# Sheet1.net
KiCad netlist of a schematic drawn in Altium Designer
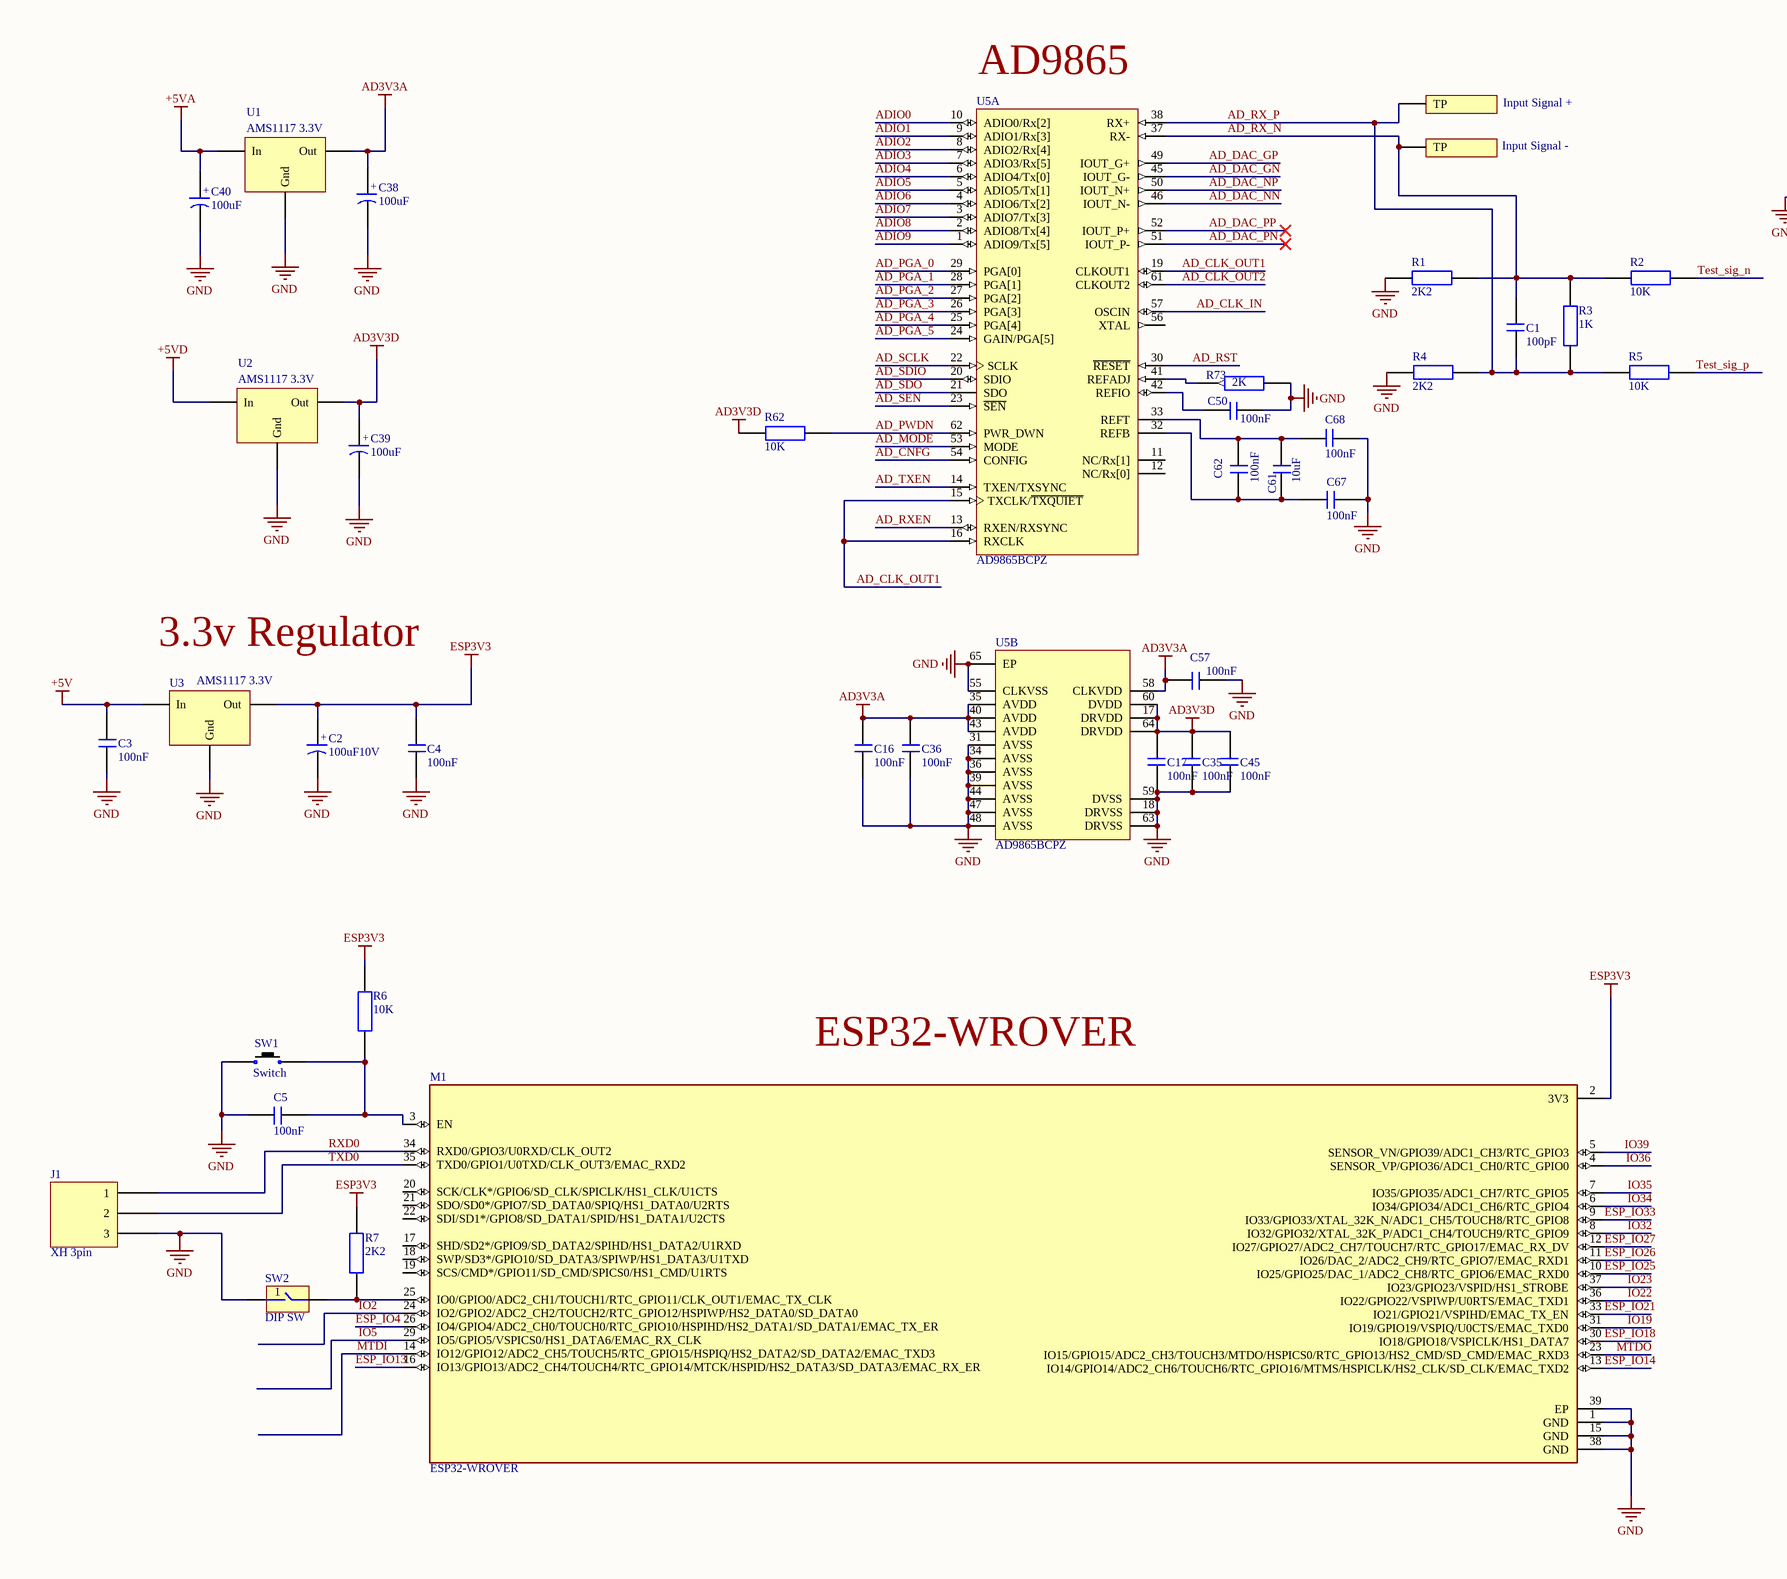
[diagram p0: Sheet1.SchDoc, left]
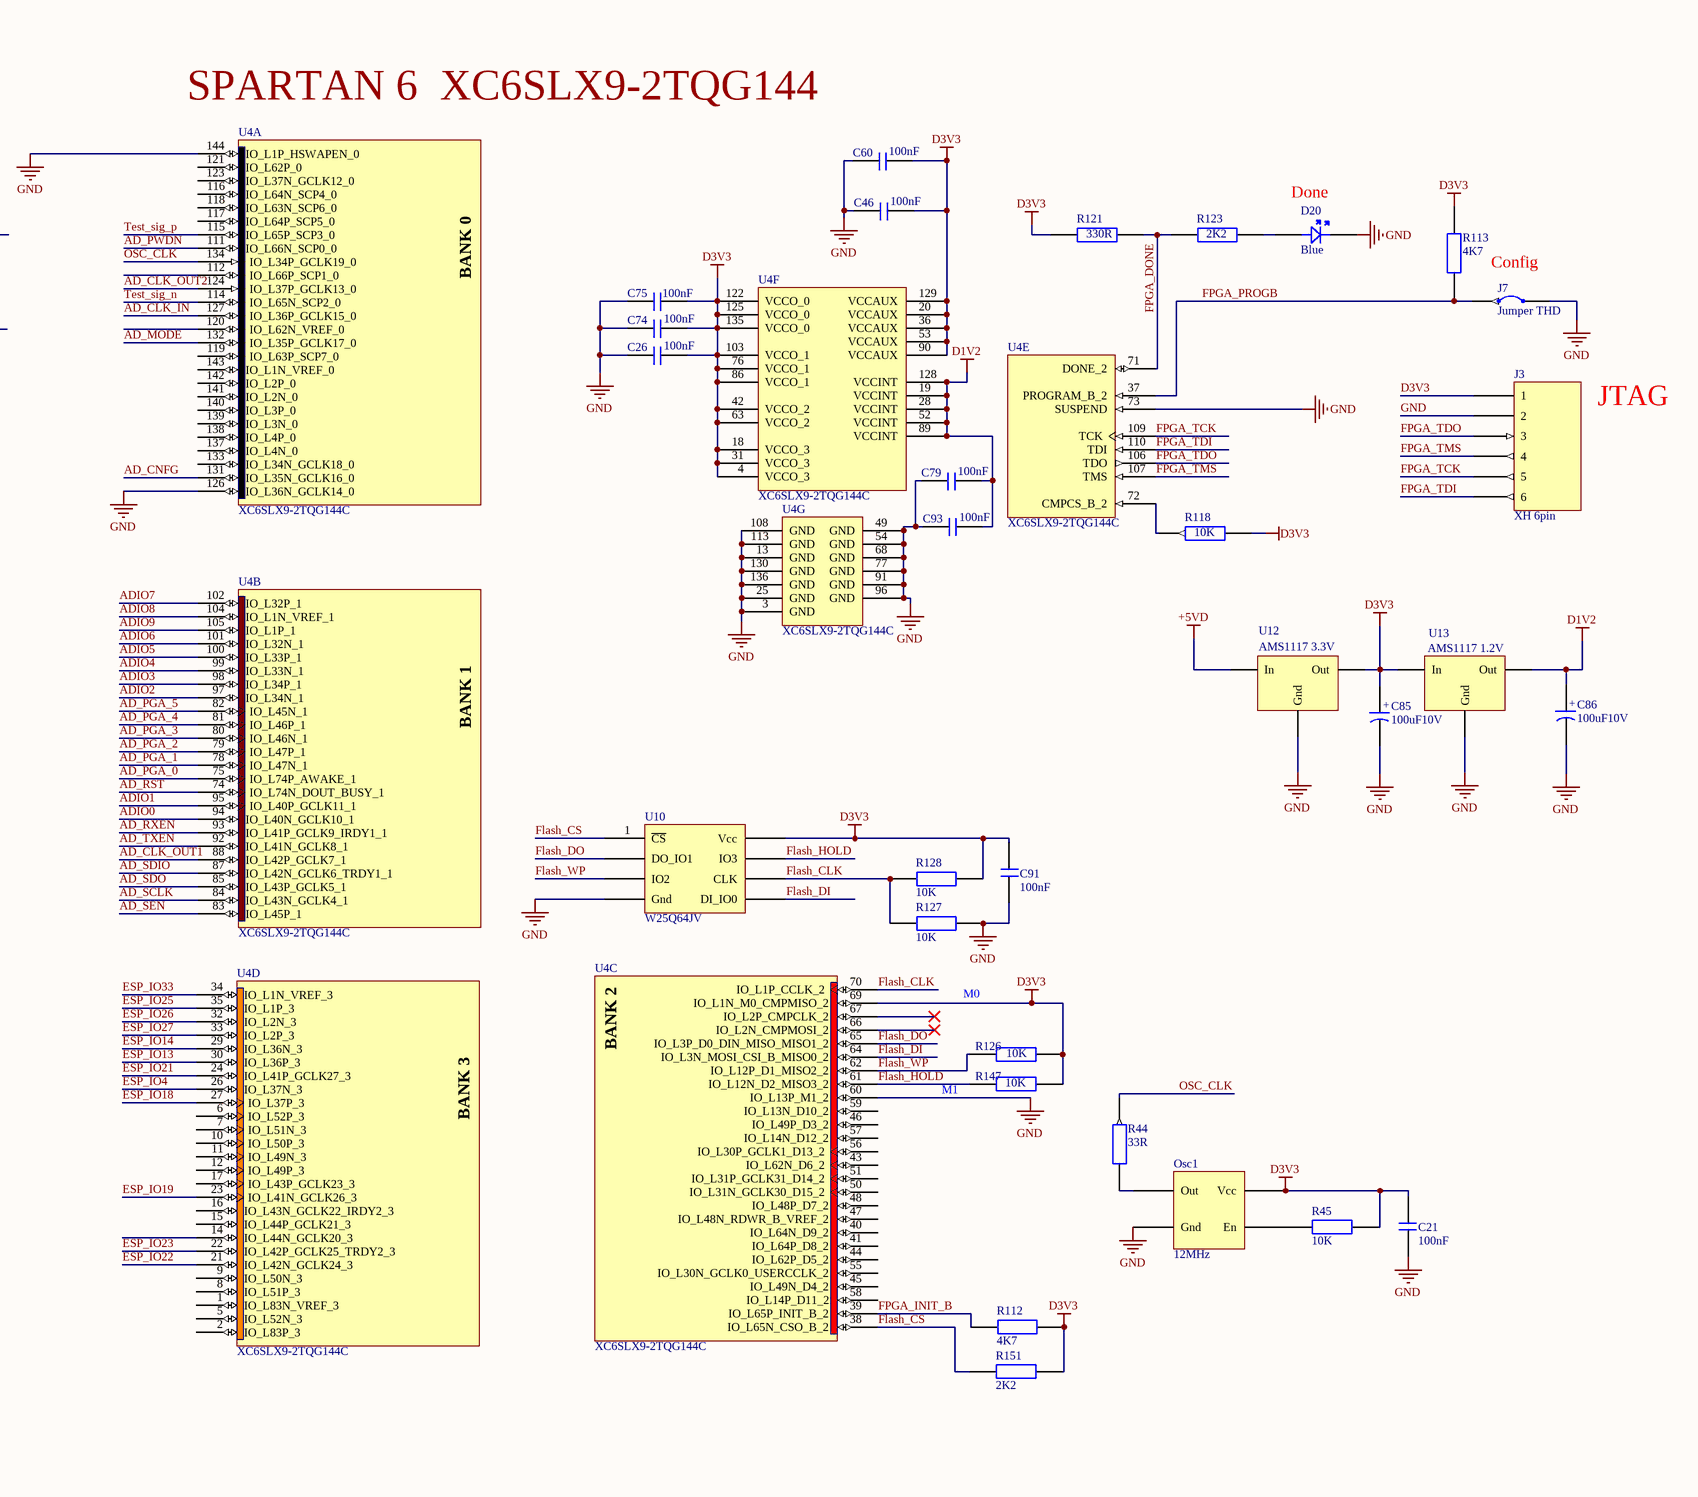
[diagram p1: Sheet1.SchDoc, right]

(export (version "E")
  (design (tool "Eeschema 10.0.6"))
  (components
    (comp (ref "C1")
      (value "100pF")
      (footprint "CAP_0805")
      (description "Capacitor SMD 0805")
      (libsource (lib "My_Integrated_Library") (part "Cap0805"))
    )
    (comp (ref "C2")
      (value "100uF10V")
      (footprint "Cap_Tan_Size_B")
      (description "Capacitor SMD Tantalium Size B")
      (libsource (lib "My_Integrated_Library") (part "Cap_Tant_B"))
    )
    (comp (ref "C3")
      (value "100nF")
      (footprint "CAP_0805")
      (description "Capacitor SMD 0805")
      (libsource (lib "My_Integrated_Library") (part "Cap0805"))
    )
    (comp (ref "C4")
      (value "100nF")
      (footprint "CAP_0805")
      (description "Capacitor SMD 0805")
      (libsource (lib "My_Integrated_Library") (part "Cap0805"))
    )
    (comp (ref "C5")
      (value "100nF")
      (footprint "CAP_0805")
      (description "Capacitor SMD 0805")
      (libsource (lib "My_Integrated_Library") (part "Cap0805"))
    )
    (comp (ref "C16")
      (value "100nF")
      (footprint "CAP_0805")
      (description "Capacitor SMD 0805")
      (libsource (lib "My_Integrated_Library") (part "Cap0805"))
    )
    (comp (ref "C17")
      (value "100nF")
      (footprint "CAP_0805")
      (description "Capacitor SMD 0805")
      (libsource (lib "My_Integrated_Library") (part "Cap0805"))
    )
    (comp (ref "C21")
      (value "100nF")
      (footprint "CAP_0805")
      (description "Capacitor SMD 0805")
      (libsource (lib "My_Integrated_Library") (part "Cap0805"))
    )
    (comp (ref "C26")
      (value "100nF")
      (footprint "CAP_0805")
      (description "Capacitor SMD 0805")
      (libsource (lib "My_Integrated_Library") (part "Cap0805"))
    )
    (comp (ref "C35")
      (value "100nF")
      (footprint "CAP_0805")
      (description "Capacitor SMD 0805")
      (libsource (lib "My_Integrated_Library") (part "Cap0805"))
    )
    (comp (ref "C36")
      (value "100nF")
      (footprint "CAP_0805")
      (description "Capacitor SMD 0805")
      (libsource (lib "My_Integrated_Library") (part "Cap0805"))
    )
    (comp (ref "C38")
      (value "100uF")
      (footprint "Cap_Tan_Size_B")
      (description "Capacitor SMD Tantalium Size B")
      (libsource (lib "My_Integrated_Library") (part "Cap_Tant_B"))
    )
    (comp (ref "C39")
      (value "100uF")
      (footprint "Cap_Tan_Size_B")
      (description "Capacitor SMD Tantalium Size B")
      (libsource (lib "My_Integrated_Library") (part "Cap_Tant_B"))
    )
    (comp (ref "C40")
      (value "100uF")
      (footprint "Cap_Tan_Size_B")
      (description "Capacitor SMD Tantalium Size B")
      (libsource (lib "My_Integrated_Library") (part "Cap_Tant_B"))
    )
    (comp (ref "C45")
      (value "100nF")
      (footprint "CAP_0805")
      (description "Capacitor SMD 0805")
      (libsource (lib "My_Integrated_Library") (part "Cap0805"))
    )
    (comp (ref "C46")
      (value "100nF")
      (footprint "CAP_0805")
      (description "Capacitor SMD 0805")
      (libsource (lib "My_Integrated_Library") (part "Cap0805"))
    )
    (comp (ref "C50")
      (value "100nF")
      (footprint "CAP_0805")
      (description "Capacitor SMD 0805")
      (libsource (lib "My_Integrated_Library") (part "Cap0805"))
    )
    (comp (ref "C57")
      (value "100nF")
      (footprint "CAP_0805")
      (description "Capacitor SMD 0805")
      (libsource (lib "My_Integrated_Library") (part "Cap0805"))
    )
    (comp (ref "C60")
      (value "100nF")
      (footprint "CAP_0805")
      (description "Capacitor SMD 0805")
      (libsource (lib "My_Integrated_Library") (part "Cap0805"))
    )
    (comp (ref "C61")
      (value "10uF")
      (footprint "CAP_0805")
      (description "Capacitor SMD 0805")
      (libsource (lib "My_Integrated_Library") (part "Cap0805"))
    )
    (comp (ref "C62")
      (value "100nF")
      (footprint "CAP_0805")
      (description "Capacitor SMD 0805")
      (libsource (lib "My_Integrated_Library") (part "Cap0805"))
    )
    (comp (ref "C67")
      (value "100nF")
      (footprint "CAP_0805")
      (description "Capacitor SMD 0805")
      (libsource (lib "My_Integrated_Library") (part "Cap0805"))
    )
    (comp (ref "C68")
      (value "100nF")
      (footprint "CAP_0805")
      (description "Capacitor SMD 0805")
      (libsource (lib "My_Integrated_Library") (part "Cap0805"))
    )
    (comp (ref "C74")
      (value "100nF")
      (footprint "CAP_0805")
      (description "Capacitor SMD 0805")
      (libsource (lib "My_Integrated_Library") (part "Cap0805"))
    )
    (comp (ref "C75")
      (value "100nF")
      (footprint "CAP_0805")
      (description "Capacitor SMD 0805")
      (libsource (lib "My_Integrated_Library") (part "Cap0805"))
    )
    (comp (ref "C79")
      (value "100nF")
      (footprint "CAP_0805")
      (description "Capacitor SMD 0805")
      (libsource (lib "My_Integrated_Library") (part "Cap0805"))
    )
    (comp (ref "C85")
      (value "100uF10V")
      (footprint "Cap_Tan_Size_B")
      (description "Capacitor SMD Tantalium Size B")
      (libsource (lib "My_Integrated_Library") (part "Cap_Tant_B"))
    )
    (comp (ref "C86")
      (value "100uF10V")
      (footprint "Cap_Tan_Size_B")
      (description "Capacitor SMD Tantalium Size B")
      (libsource (lib "My_Integrated_Library") (part "Cap_Tant_B"))
    )
    (comp (ref "C91")
      (value "100nF")
      (footprint "CAP_0805")
      (description "Capacitor SMD 0805")
      (libsource (lib "My_Integrated_Library") (part "Cap0805"))
    )
    (comp (ref "C93")
      (value "100nF")
      (footprint "CAP_0805")
      (description "Capacitor SMD 0805")
      (libsource (lib "My_Integrated_Library") (part "Cap0805"))
    )
    (comp (ref "D20")
      (value "Blue")
      (footprint "LED_0805_Blue")
      (description "LED SMD 0805 Blue")
      (libsource (lib "My_Integrated_Library") (part "LED_0805_Blue"))
    )
    (comp (ref "J1")
      (value "XH 3pin")
      (footprint "XH-3pin")
      (description "Connector XH Female 3-pin")
      (libsource (lib "My_Integrated_Library") (part "Con_XH_3pin"))
    )
    (comp (ref "J3")
      (value "XH 6pin")
      (footprint "XH-6pin")
      (description "Connector XH Female 6-pin")
      (libsource (lib "My_Integrated_Library") (part "Con_XH_6pin"))
    )
    (comp (ref "J7")
      (value "Jumper THD")
      (footprint "Jumper_2pin")
      (description "Jumper pin header + jumper 2pin pirch=2.54mm")
      (libsource (lib "My_Integrated_Library") (part "Jumper DIP"))
    )
    (comp (ref "M1")
      (value "ESP32-WROVER")
      (footprint "ESP32-WROVER")
      (fields (field (name "MF") "Espressif Systems"))
      (libsource (lib "My_Integrated_Library") (part "ESP32-WROVER"))
    )
    (comp (ref "Osc1")
      (value "12MHz")
      (footprint "Osc_SMD_5x7")
      (description "Oscillator SMD 5x7")
      (libsource (lib "My_Integrated_Library") (part "Osc_SMD"))
    )
    (comp (ref "R1")
      (value "2K2")
      (footprint "RES_0805")
      (description "Resistor SMD 0805")
      (libsource (lib "My_Integrated_Library") (part "Res0805"))
    )
    (comp (ref "R2")
      (value "10K")
      (footprint "RES_0805")
      (description "Resistor SMD 0805")
      (libsource (lib "My_Integrated_Library") (part "Res0805"))
    )
    (comp (ref "R3")
      (value "1K")
      (footprint "RES_0805")
      (description "Resistor SMD 0805")
      (libsource (lib "My_Integrated_Library") (part "Res0805"))
    )
    (comp (ref "R4")
      (value "2K2")
      (footprint "RES_0805")
      (description "Resistor SMD 0805")
      (libsource (lib "My_Integrated_Library") (part "Res0805"))
    )
    (comp (ref "R5")
      (value "10K")
      (footprint "RES_0805")
      (description "Resistor SMD 0805")
      (libsource (lib "My_Integrated_Library") (part "Res0805"))
    )
    (comp (ref "R6")
      (value "10K")
      (footprint "RES_0805")
      (description "Resistor SMD 0805")
      (libsource (lib "My_Integrated_Library") (part "Res0805"))
    )
    (comp (ref "R7")
      (value "2K2")
      (footprint "RES_0805")
      (description "Resistor SMD 0805")
      (libsource (lib "My_Integrated_Library") (part "Res0805"))
    )
    (comp (ref "R44")
      (value "33R")
      (footprint "RES_0805")
      (description "Resistor SMD 0805")
      (libsource (lib "My_Integrated_Library") (part "Res0805"))
    )
    (comp (ref "R45")
      (value "10K")
      (footprint "RES_0805")
      (description "Resistor SMD 0805")
      (libsource (lib "My_Integrated_Library") (part "Res0805"))
    )
    (comp (ref "R62")
      (value "10K")
      (footprint "RES_0805")
      (description "Resistor SMD 0805")
      (libsource (lib "My_Integrated_Library") (part "Res0805"))
    )
    (comp (ref "R73")
      (value "2K")
      (footprint "RES_0805")
      (description "Resistor SMD 0805")
      (libsource (lib "My_Integrated_Library") (part "Res0805"))
    )
    (comp (ref "R112")
      (value "4K7")
      (footprint "RES_0805")
      (description "Resistor SMD 0805")
      (libsource (lib "My_Integrated_Library") (part "Res0805"))
    )
    (comp (ref "R113")
      (value "4K7")
      (footprint "RES_0805")
      (description "Resistor SMD 0805")
      (libsource (lib "My_Integrated_Library") (part "Res0805"))
    )
    (comp (ref "R118")
      (value "10K")
      (footprint "RES_0805")
      (description "Resistor SMD 0805")
      (libsource (lib "My_Integrated_Library") (part "Res0805"))
    )
    (comp (ref "R121")
      (value "330R")
      (footprint "RES_0805")
      (description "Resistor SMD 0805")
      (libsource (lib "My_Integrated_Library") (part "Res0805"))
    )
    (comp (ref "R123")
      (value "2K2")
      (footprint "RES_0805")
      (description "Resistor SMD 0805")
      (libsource (lib "My_Integrated_Library") (part "Res0805"))
    )
    (comp (ref "R126")
      (value "10K")
      (footprint "RES_0805")
      (description "Resistor SMD 0805")
      (libsource (lib "My_Integrated_Library") (part "Res0805"))
    )
    (comp (ref "R127")
      (value "10K")
      (footprint "RES_0805")
      (description "Resistor SMD 0805")
      (libsource (lib "My_Integrated_Library") (part "Res0805"))
    )
    (comp (ref "R128")
      (value "10K")
      (footprint "RES_0805")
      (description "Resistor SMD 0805")
      (libsource (lib "My_Integrated_Library") (part "Res0805"))
    )
    (comp (ref "R147")
      (value "10K")
      (footprint "RES_0805")
      (description "Resistor SMD 0805")
      (libsource (lib "My_Integrated_Library") (part "Res0805"))
    )
    (comp (ref "R151")
      (value "2K2")
      (footprint "RES_0805")
      (description "Resistor SMD 0805")
      (libsource (lib "My_Integrated_Library") (part "Res0805"))
    )
    (comp (ref "SW1")
      (value "Switch")
      (footprint "Tact_SW_SMD")
      (description "Tact switch SMD 2pin")
      (libsource (lib "My_Integrated_Library") (part "Tact_sw"))
    )
    (comp (ref "SW2")
      (value "DIP SW")
      (footprint "DIP_SW_1key")
      (description "DIP Swtich 1 key")
      (libsource (lib "My_Integrated_Library") (part "DIP_SW_1"))
    )
    (comp (ref "TP1")
      (value "Input Signal +")
      (footprint "TP")
      (description "Test point")
      (libsource (lib "My_Integrated_Library") (part "TP"))
    )
    (comp (ref "TP2")
      (value "Input Signal -")
      (footprint "TP")
      (description "Test point")
      (libsource (lib "My_Integrated_Library") (part "TP"))
    )
    (comp (ref "U1")
      (value "AMS1117 3.3V")
      (footprint "AMS1117-SOT223")
      (description "AMS1117 Regulator 3.3V SMD SOT223")
      (libsource (lib "My_Integrated_Library") (part "AMS1117-SOT223"))
    )
    (comp (ref "U2")
      (value "AMS1117 3.3V")
      (footprint "AMS1117-SOT223")
      (description "AMS1117 Regulator 3.3V SMD SOT223")
      (libsource (lib "My_Integrated_Library") (part "AMS1117-SOT223"))
    )
    (comp (ref "U3")
      (value "AMS1117 3.3V")
      (footprint "AMS1117-SOT223")
      (description "AMS1117 Regulator 3.3V SMD SOT223")
      (libsource (lib "My_Integrated_Library") (part "AMS1117-SOT223"))
    )
    (comp (ref "U4")
      (value "XC6SLX9-2TQG144C")
      (footprint "XILINX-TQG144_M")
      (libsource (lib "") (part "XC6SLX9-2TQG144C_1"))
    )
    (comp (ref "U5")
      (value "AD9865BCPZ")
      (footprint "LFCSP_64Lead")
      (description "Broadband Modem Mixed-Signal Front End, 80MSPS, -40 to +85 degC, CP-64-3, Pb-Free, Tray")
      (fields (field (name "GENERIC PART NUMBER") "AD9865") (field (name "MANUFACTURER") "Analog Devices"))
      (libsource (lib "My_Integrated_Library") (part "AD9865BCPZ"))
    )
    (comp (ref "U10")
      (value "W25Q64JV")
      (footprint "W25Q64")
      (description "Serial Flash Memory 64Mbit")
      (libsource (lib "My_Integrated_Library") (part "W25Q64JV"))
    )
    (comp (ref "U12")
      (value "AMS1117 3.3V")
      (footprint "AMS1117-SOT223")
      (description "AMS1117 Regulator 3.3V SMD SOT223")
      (libsource (lib "My_Integrated_Library") (part "AMS1117-SOT223"))
    )
    (comp (ref "U13")
      (value "AMS1117 1.2V")
      (footprint "AMS1117-SOT223")
      (description "AMS1117 Regulator 3.3V SMD SOT223")
      (libsource (lib "My_Integrated_Library") (part "AMS1117-SOT223"))
    )
  )
  (nets
    (net (code "1") (name "+5V") (class "Default")
      (node (ref "C3") (pin "2") (pinfunction "2_2") (pintype "passive"))
      (node (ref "U3") (pin "1") (pinfunction "In_1") (pintype "passive"))
    )
    (net (code "2") (name "+5VA") (class "Default")
      (node (ref "C40") (pin "+") (pinfunction "+_+") (pintype "passive"))
      (node (ref "U1") (pin "1") (pinfunction "In_1") (pintype "passive"))
    )
    (net (code "3") (name "+5VD") (class "Default")
      (node (ref "U12") (pin "1") (pinfunction "In_1") (pintype "passive"))
      (node (ref "U2") (pin "1") (pinfunction "In_1") (pintype "passive"))
    )
    (net (code "4") (name "/ADIO0") (class "Default")
      (node (ref "U4") (pin "94") (pinfunction "IO_L40N_GCLK10_1_94") (pintype "bidirectional"))
      (node (ref "U5") (pin "10") (pinfunction "ADIO0/Rx[2]_10") (pintype "bidirectional"))
    )
    (net (code "5") (name "/ADIO1") (class "Default")
      (node (ref "U4") (pin "95") (pinfunction "IO_L40P_GCLK11_1_95") (pintype "bidirectional"))
      (node (ref "U5") (pin "9") (pinfunction "ADIO1/Rx[3]_9") (pintype "bidirectional"))
    )
    (net (code "6") (name "/ADIO2") (class "Default")
      (node (ref "U4") (pin "97") (pinfunction "IO_L34N_1_97") (pintype "bidirectional"))
      (node (ref "U5") (pin "8") (pinfunction "ADIO2/Rx[4]_8") (pintype "bidirectional"))
    )
    (net (code "7") (name "/ADIO3") (class "Default")
      (node (ref "U4") (pin "98") (pinfunction "IO_L34P_1_98") (pintype "bidirectional"))
      (node (ref "U5") (pin "7") (pinfunction "ADIO3/Rx[5]_7") (pintype "bidirectional"))
    )
    (net (code "8") (name "/ADIO4") (class "Default")
      (node (ref "U4") (pin "99") (pinfunction "IO_L33N_1_99") (pintype "bidirectional"))
      (node (ref "U5") (pin "6") (pinfunction "ADIO4/Tx[0]_6") (pintype "bidirectional"))
    )
    (net (code "9") (name "/ADIO5") (class "Default")
      (node (ref "U4") (pin "100") (pinfunction "IO_L33P_1_100") (pintype "bidirectional"))
      (node (ref "U5") (pin "5") (pinfunction "ADIO5/Tx[1]_5") (pintype "bidirectional"))
    )
    (net (code "10") (name "/ADIO6") (class "Default")
      (node (ref "U4") (pin "101") (pinfunction "IO_L32N_1_101") (pintype "bidirectional"))
      (node (ref "U5") (pin "4") (pinfunction "ADIO6/Tx[2]_4") (pintype "bidirectional"))
    )
    (net (code "11") (name "/ADIO7") (class "Default")
      (node (ref "U4") (pin "102") (pinfunction "IO_L32P_1_102") (pintype "bidirectional"))
      (node (ref "U5") (pin "3") (pinfunction "ADIO7/Tx[3]_3") (pintype "bidirectional"))
    )
    (net (code "12") (name "/ADIO8") (class "Default")
      (node (ref "U4") (pin "104") (pinfunction "IO_L1N_VREF_1_104") (pintype "bidirectional"))
      (node (ref "U5") (pin "2") (pinfunction "ADIO8/Tx[4]_2") (pintype "bidirectional"))
    )
    (net (code "13") (name "/ADIO9") (class "Default")
      (node (ref "U4") (pin "105") (pinfunction "IO_L1P_1_105") (pintype "bidirectional"))
      (node (ref "U5") (pin "1") (pinfunction "ADIO9/Tx[5]_1") (pintype "bidirectional"))
    )
    (net (code "14") (name "/AD_CLK_IN") (class "Default")
      (node (ref "U4") (pin "127") (pinfunction "IO_L36P_GCLK15_0_127") (pintype "bidirectional"))
      (node (ref "U5") (pin "57") (pinfunction "OSCIN_57") (pintype "bidirectional"))
    )
    (net (code "15") (name "/AD_CLK_OUT1") (class "Default")
      (node (ref "U4") (pin "88") (pinfunction "IO_L42P_GCLK7_1_88") (pintype "bidirectional"))
      (node (ref "U5") (pin "15") (pinfunction "TXCLK/~{TXQUIET}_15") (pintype "input"))
      (node (ref "U5") (pin "16") (pinfunction "RXCLK_16") (pintype "input"))
      (node (ref "U5") (pin "19") (pinfunction "CLKOUT1_19") (pintype "bidirectional"))
    )
    (net (code "16") (name "/AD_CLK_OUT2") (class "Default")
      (node (ref "U4") (pin "124") (pinfunction "IO_L37P_GCLK13_0_124") (pintype "input"))
      (node (ref "U5") (pin "61") (pinfunction "CLKOUT2_61") (pintype "bidirectional"))
    )
    (net (code "17") (name "/AD_CNFG") (class "Default")
      (node (ref "U4") (pin "131") (pinfunction "IO_L35N_GCLK16_0_131") (pintype "bidirectional"))
      (node (ref "U5") (pin "54") (pinfunction "CONFIG_54") (pintype "input"))
    )
    (net (code "18") (name "/AD_DAC_GN") (class "Default")
      (node (ref "U5") (pin "45") (pinfunction "IOUT_G-_45") (pintype "output"))
    )
    (net (code "19") (name "/AD_DAC_GP") (class "Default")
      (node (ref "U5") (pin "49") (pinfunction "IOUT_G+_49") (pintype "output"))
    )
    (net (code "20") (name "/AD_DAC_NN") (class "Default")
      (node (ref "U5") (pin "46") (pinfunction "IOUT_N-_46") (pintype "output"))
    )
    (net (code "21") (name "/AD_DAC_NP") (class "Default")
      (node (ref "U5") (pin "50") (pinfunction "IOUT_N+_50") (pintype "output"))
    )
    (net (code "22") (name "/AD_DAC_PN") (class "Default")
      (node (ref "U5") (pin "51") (pinfunction "IOUT_P-_51") (pintype "output+no_connect"))
    )
    (net (code "23") (name "/AD_DAC_PP") (class "Default")
      (node (ref "U5") (pin "52") (pinfunction "IOUT_P+_52") (pintype "output+no_connect"))
    )
    (net (code "24") (name "/AD_MODE") (class "Default")
      (node (ref "U4") (pin "132") (pinfunction "IO_L35P_GCLK17_0_132") (pintype "bidirectional"))
      (node (ref "U5") (pin "53") (pinfunction "MODE_53") (pintype "input"))
    )
    (net (code "25") (name "/AD_PGA_0") (class "Default")
      (node (ref "U4") (pin "75") (pinfunction "IO_L74P_AWAKE_1_75") (pintype "bidirectional"))
      (node (ref "U5") (pin "29") (pinfunction "PGA[0]_29") (pintype "input"))
    )
    (net (code "26") (name "/AD_PGA_1") (class "Default")
      (node (ref "U4") (pin "78") (pinfunction "IO_L47N_1_78") (pintype "bidirectional"))
      (node (ref "U5") (pin "28") (pinfunction "PGA[1]_28") (pintype "input"))
    )
    (net (code "27") (name "/AD_PGA_2") (class "Default")
      (node (ref "U4") (pin "79") (pinfunction "IO_L47P_1_79") (pintype "bidirectional"))
      (node (ref "U5") (pin "27") (pinfunction "PGA[2]_27") (pintype "input"))
    )
    (net (code "28") (name "/AD_PGA_3") (class "Default")
      (node (ref "U4") (pin "80") (pinfunction "IO_L46N_1_80") (pintype "bidirectional"))
      (node (ref "U5") (pin "26") (pinfunction "PGA[3]_26") (pintype "input"))
    )
    (net (code "29") (name "/AD_PGA_4") (class "Default")
      (node (ref "U4") (pin "81") (pinfunction "IO_L46P_1_81") (pintype "bidirectional"))
      (node (ref "U5") (pin "25") (pinfunction "PGA[4]_25") (pintype "input"))
    )
    (net (code "30") (name "/AD_PGA_5") (class "Default")
      (node (ref "U4") (pin "82") (pinfunction "IO_L45N_1_82") (pintype "bidirectional"))
      (node (ref "U5") (pin "24") (pinfunction "GAIN/PGA[5]_24") (pintype "input"))
    )
    (net (code "31") (name "/AD_PWDN") (class "Default")
      (node (ref "R62") (pin "2") (pinfunction "2_2") (pintype "passive"))
      (node (ref "U4") (pin "111") (pinfunction "IO_L66N_SCP0_0_111") (pintype "bidirectional"))
      (node (ref "U5") (pin "62") (pinfunction "PWR_DWN_62") (pintype "input"))
    )
    (net (code "32") (name "/AD_RST") (class "Default")
      (node (ref "U4") (pin "74") (pinfunction "IO_L74N_DOUT_BUSY_1_74") (pintype "bidirectional"))
      (node (ref "U5") (pin "30") (pinfunction "~{RESET}_30") (pintype "input"))
    )
    (net (code "33") (name "/AD_RXEN") (class "Default")
      (node (ref "U4") (pin "93") (pinfunction "IO_L41P_GCLK9_IRDY1_1_93") (pintype "bidirectional"))
      (node (ref "U5") (pin "13") (pinfunction "RXEN/RXSYNC_13") (pintype "bidirectional"))
    )
    (net (code "34") (name "/AD_RX_N") (class "Default")
      (node (ref "C1") (pin "1") (pinfunction "1_1") (pintype "passive"))
      (node (ref "R1") (pin "1") (pinfunction "1_1") (pintype "passive"))
      (node (ref "R2") (pin "2") (pinfunction "2_2") (pintype "passive"))
      (node (ref "R3") (pin "1") (pinfunction "1_1") (pintype "passive"))
      (node (ref "TP2") (pin "1") (pinfunction "TP_1") (pintype "passive"))
      (node (ref "U5") (pin "37") (pinfunction "RX-_37") (pintype "input"))
    )
    (net (code "35") (name "/AD_RX_P") (class "Default")
      (node (ref "C1") (pin "2") (pinfunction "2_2") (pintype "passive"))
      (node (ref "R3") (pin "2") (pinfunction "2_2") (pintype "passive"))
      (node (ref "R4") (pin "1") (pinfunction "1_1") (pintype "passive"))
      (node (ref "R5") (pin "2") (pinfunction "2_2") (pintype "passive"))
      (node (ref "TP1") (pin "1") (pinfunction "TP_1") (pintype "passive"))
      (node (ref "U5") (pin "38") (pinfunction "RX+_38") (pintype "input"))
    )
    (net (code "36") (name "/AD_SCLK") (class "Default")
      (node (ref "U4") (pin "84") (pinfunction "IO_L43N_GCLK4_1_84") (pintype "bidirectional"))
      (node (ref "U5") (pin "22") (pinfunction "SCLK_22") (pintype "input"))
    )
    (net (code "37") (name "/AD_SDIO") (class "Default")
      (node (ref "U4") (pin "87") (pinfunction "IO_L42N_GCLK6_TRDY1_1_87") (pintype "bidirectional"))
      (node (ref "U5") (pin "20") (pinfunction "SDIO_20") (pintype "bidirectional"))
    )
    (net (code "38") (name "/AD_SDO") (class "Default")
      (node (ref "U4") (pin "85") (pinfunction "IO_L43P_GCLK5_1_85") (pintype "bidirectional"))
      (node (ref "U5") (pin "21") (pinfunction "SDO_21") (pintype "tri_state"))
    )
    (net (code "39") (name "/AD_SEN") (class "Default")
      (node (ref "U4") (pin "83") (pinfunction "IO_L45P_1_83") (pintype "bidirectional"))
      (node (ref "U5") (pin "23") (pinfunction "~{SEN}_23") (pintype "input"))
    )
    (net (code "40") (name "/AD_TXEN") (class "Default")
      (node (ref "U4") (pin "92") (pinfunction "IO_L41N_GCLK8_1_92") (pintype "bidirectional"))
      (node (ref "U5") (pin "14") (pinfunction "TXEN/TXSYNC_14") (pintype "input"))
    )
    (net (code "41") (name "/ESP_IO4") (class "Default")
      (node (ref "M1") (pin "26") (pinfunction "IO4/GPIO4/ADC2_CH0/TOUCH0/RTC_GPIO10/HSPIHD/HS2_DATA1/SD_DATA1/EMAC_TX_ER_26") (pintype "bidirectional"))
      (node (ref "U4") (pin "26") (pinfunction "IO_L37N_3_26") (pintype "bidirectional"))
    )
    (net (code "42") (name "/ESP_IO13") (class "Default")
      (node (ref "M1") (pin "16") (pinfunction "IO13/GPIO13/ADC2_CH4/TOUCH4/RTC_GPIO14/MTCK/HSPID/HS2_DATA3/SD_DATA3/EMAC_RX_ER_16") (pintype "bidirectional"))
      (node (ref "U4") (pin "30") (pinfunction "IO_L36P_3_30") (pintype "bidirectional"))
    )
    (net (code "43") (name "/ESP_IO14") (class "Default")
      (node (ref "M1") (pin "13") (pinfunction "IO14/GPIO14/ADC2_CH6/TOUCH6/RTC_GPIO16/MTMS/HSPICLK/HS2_CLK/SD_CLK/EMAC_TXD2_13") (pintype "bidirectional"))
      (node (ref "U4") (pin "29") (pinfunction "IO_L36N_3_29") (pintype "bidirectional"))
    )
    (net (code "44") (name "/ESP_IO18") (class "Default")
      (node (ref "M1") (pin "30") (pinfunction "IO18/GPIO18/VSPICLK/HS1_DATA7_30") (pintype "bidirectional"))
      (node (ref "U4") (pin "27") (pinfunction "IO_L37P_3_27") (pintype "bidirectional"))
    )
    (net (code "45") (name "/ESP_IO19") (class "Default")
      (node (ref "U4") (pin "23") (pinfunction "IO_L41N_GCLK26_3_23") (pintype "bidirectional"))
    )
    (net (code "46") (name "/ESP_IO21") (class "Default")
      (node (ref "M1") (pin "33") (pinfunction "IO21/GPIO21/VSPIHD/EMAC_TX_EN_33") (pintype "bidirectional"))
      (node (ref "U4") (pin "24") (pinfunction "IO_L41P_GCLK27_3_24") (pintype "bidirectional"))
    )
    (net (code "47") (name "/ESP_IO22") (class "Default")
      (node (ref "U4") (pin "21") (pinfunction "IO_L42N_GCLK24_3_21") (pintype "bidirectional"))
    )
    (net (code "48") (name "/ESP_IO23") (class "Default")
      (node (ref "U4") (pin "22") (pinfunction "IO_L42P_GCLK25_TRDY2_3_22") (pintype "bidirectional"))
    )
    (net (code "49") (name "/ESP_IO25") (class "Default")
      (node (ref "M1") (pin "10") (pinfunction "IO25/GPIO25/DAC_1/ADC2_CH8/RTC_GPIO6/EMAC_RXD0_10") (pintype "bidirectional"))
      (node (ref "U4") (pin "35") (pinfunction "IO_L1P_3_35") (pintype "bidirectional"))
    )
    (net (code "50") (name "/ESP_IO26") (class "Default")
      (node (ref "M1") (pin "11") (pinfunction "IO26/DAC_2/ADC2_CH9/RTC_GPIO7/EMAC_RXD1_11") (pintype "bidirectional"))
      (node (ref "U4") (pin "32") (pinfunction "IO_L2N_3_32") (pintype "bidirectional"))
    )
    (net (code "51") (name "/ESP_IO27") (class "Default")
      (node (ref "M1") (pin "12") (pinfunction "IO27/GPIO27/ADC2_CH7/TOUCH7/RTC_GPIO17/EMAC_RX_DV_12") (pintype "bidirectional"))
      (node (ref "U4") (pin "33") (pinfunction "IO_L2P_3_33") (pintype "bidirectional"))
    )
    (net (code "52") (name "/ESP_IO33") (class "Default")
      (node (ref "M1") (pin "9") (pinfunction "IO33/GPIO33/XTAL_32K_N/ADC1_CH5/TOUCH8/RTC_GPIO8_9") (pintype "bidirectional"))
      (node (ref "U4") (pin "34") (pinfunction "IO_L1N_VREF_3_34") (pintype "bidirectional"))
    )
    (net (code "53") (name "/FPGA_DONE") (class "Default")
      (node (ref "R121") (pin "2") (pinfunction "2_2") (pintype "passive"))
      (node (ref "R123") (pin "1") (pinfunction "1_1") (pintype "passive"))
      (node (ref "U4") (pin "71") (pinfunction "DONE_2_71") (pintype "bidirectional"))
    )
    (net (code "54") (name "/FPGA_INIT_B") (class "Default")
      (node (ref "R112") (pin "1") (pinfunction "1_1") (pintype "passive"))
      (node (ref "U4") (pin "39") (pinfunction "IO_L65P_INIT_B_2_39") (pintype "bidirectional"))
    )
    (net (code "55") (name "/FPGA_PROGB") (class "Default")
      (node (ref "J7") (pin "2") (pinfunction "2_2") (pintype "output"))
      (node (ref "R113") (pin "1") (pinfunction "1_1") (pintype "passive"))
      (node (ref "U4") (pin "37") (pinfunction "PROGRAM_B_2_37") (pintype "input"))
    )
    (net (code "56") (name "/FPGA_TCK") (class "Default")
      (node (ref "J3") (pin "5") (pinfunction "5_5") (pintype "output"))
      (node (ref "U4") (pin "109") (pinfunction "TCK_109") (pintype "input"))
    )
    (net (code "57") (name "/FPGA_TDI") (class "Default")
      (node (ref "J3") (pin "6") (pinfunction "6_6") (pintype "output"))
      (node (ref "U4") (pin "110") (pinfunction "TDI_110") (pintype "input"))
    )
    (net (code "58") (name "/FPGA_TDO") (class "Default")
      (node (ref "J3") (pin "3") (pinfunction "3_3") (pintype "input"))
      (node (ref "U4") (pin "106") (pinfunction "TDO_106") (pintype "output"))
    )
    (net (code "59") (name "/FPGA_TMS") (class "Default")
      (node (ref "J3") (pin "4") (pinfunction "4_4") (pintype "output"))
      (node (ref "U4") (pin "107") (pinfunction "TMS_107") (pintype "input"))
    )
    (net (code "60") (name "/Flash_CLK") (class "Default")
      (node (ref "R127") (pin "2") (pinfunction "2_2") (pintype "passive"))
      (node (ref "R128") (pin "1") (pinfunction "1_1") (pintype "passive"))
      (node (ref "U10") (pin "6") (pinfunction "CLK_6") (pintype "passive"))
      (node (ref "U4") (pin "70") (pinfunction "IO_L1P_CCLK_2_70") (pintype "bidirectional"))
    )
    (net (code "61") (name "/Flash_CS") (class "Default")
      (node (ref "R151") (pin "1") (pinfunction "1_1") (pintype "passive"))
      (node (ref "U10") (pin "1") (pinfunction "~{CS}_1") (pintype "passive"))
      (node (ref "U4") (pin "38") (pinfunction "IO_L65N_CSO_B_2_38") (pintype "bidirectional"))
    )
    (net (code "62") (name "/Flash_DI") (class "Default")
      (node (ref "U10") (pin "5") (pinfunction "DI_IO0_5") (pintype "passive"))
      (node (ref "U4") (pin "64") (pinfunction "IO_L3N_MOSI_CSI_B_MISO0_2_64") (pintype "bidirectional"))
    )
    (net (code "63") (name "/Flash_DO") (class "Default")
      (node (ref "U10") (pin "2") (pinfunction "DO_IO1_2") (pintype "passive"))
      (node (ref "U4") (pin "65") (pinfunction "IO_L3P_D0_DIN_MISO_MISO1_2_65") (pintype "bidirectional"))
    )
    (net (code "64") (name "/Flash_HOLD") (class "Default")
      (node (ref "R147") (pin "1") (pinfunction "1_1") (pintype "passive"))
      (node (ref "U10") (pin "7") (pinfunction "IO3_7") (pintype "passive"))
      (node (ref "U4") (pin "61") (pinfunction "IO_L12N_D2_MISO3_2_61") (pintype "bidirectional"))
    )
    (net (code "65") (name "/Flash_WP") (class "Default")
      (node (ref "R126") (pin "1") (pinfunction "1_1") (pintype "passive"))
      (node (ref "U10") (pin "3") (pinfunction "IO2_3") (pintype "passive"))
      (node (ref "U4") (pin "62") (pinfunction "IO_L12P_D1_MISO2_2_62") (pintype "bidirectional"))
    )
    (net (code "66") (name "/IO2") (class "Default")
      (node (ref "M1") (pin "24") (pinfunction "IO2/GPIO2/ADC2_CH2/TOUCH2/RTC_GPIO12/HSPIWP/HS2_DATA0/SD_DATA0_24") (pintype "bidirectional"))
    )
    (net (code "67") (name "/IO5") (class "Default")
      (node (ref "M1") (pin "29") (pinfunction "IO5/GPIO5/VSPICS0/HS1_DATA6/EMAC_RX_CLK_29") (pintype "bidirectional"))
    )
    (net (code "68") (name "/IO19") (class "Default")
      (node (ref "M1") (pin "31") (pinfunction "IO19/GPIO19/VSPIQ/U0CTS/EMAC_TXD0_31") (pintype "bidirectional"))
    )
    (net (code "69") (name "/IO22") (class "Default")
      (node (ref "M1") (pin "36") (pinfunction "IO22/GPIO22/VSPIWP/U0RTS/EMAC_TXD1_36") (pintype "bidirectional"))
    )
    (net (code "70") (name "/IO23") (class "Default")
      (node (ref "M1") (pin "37") (pinfunction "IO23/GPIO23/VSPID/HS1_STROBE_37") (pintype "bidirectional"))
    )
    (net (code "71") (name "/IO32") (class "Default")
      (node (ref "M1") (pin "8") (pinfunction "IO32/GPIO32/XTAL_32K_P/ADC1_CH4/TOUCH9/RTC_GPIO9_8") (pintype "bidirectional"))
    )
    (net (code "72") (name "/IO34") (class "Default")
      (node (ref "M1") (pin "6") (pinfunction "IO34/GPIO34/ADC1_CH6/RTC_GPIO4_6") (pintype "bidirectional"))
    )
    (net (code "73") (name "/IO35") (class "Default")
      (node (ref "M1") (pin "7") (pinfunction "IO35/GPIO35/ADC1_CH7/RTC_GPIO5_7") (pintype "bidirectional"))
    )
    (net (code "74") (name "/IO36") (class "Default")
      (node (ref "M1") (pin "4") (pinfunction "SENSOR_VP/GPIO36/ADC1_CH0/RTC_GPIO0_4") (pintype "bidirectional"))
    )
    (net (code "75") (name "/IO39") (class "Default")
      (node (ref "M1") (pin "5") (pinfunction "SENSOR_VN/GPIO39/ADC1_CH3/RTC_GPIO3_5") (pintype "bidirectional"))
    )
    (net (code "76") (name "/MTDI") (class "Default")
      (node (ref "M1") (pin "14") (pinfunction "IO12/GPIO12/ADC2_CH5/TOUCH5/RTC_GPIO15/HSPIQ/HS2_DATA2/SD_DATA2/EMAC_TXD3_14") (pintype "bidirectional"))
    )
    (net (code "77") (name "/MTDO") (class "Default")
      (node (ref "M1") (pin "23") (pinfunction "IO15/GPIO15/ADC2_CH3/TOUCH3/MTDO/HSPICS0/RTC_GPIO13/HS2_CMD/SD_CMD/EMAC_RXD3_23") (pintype "bidirectional"))
    )
    (net (code "78") (name "/OSC_CLK") (class "Default")
      (node (ref "R44") (pin "1") (pinfunction "1_1") (pintype "passive"))
      (node (ref "U4") (pin "134") (pinfunction "IO_L34P_GCLK19_0_134") (pintype "input"))
    )
    (net (code "79") (name "/RXD0") (class "Default")
      (node (ref "J1") (pin "1") (pinfunction "1_1") (pintype "passive"))
      (node (ref "M1") (pin "34") (pinfunction "RXD0/GPIO3/U0RXD/CLK_OUT2_34") (pintype "bidirectional"))
    )
    (net (code "80") (name "/TXD0") (class "Default")
      (node (ref "J1") (pin "2") (pinfunction "2_2") (pintype "passive"))
      (node (ref "M1") (pin "35") (pinfunction "TXD0/GPIO1/U0TXD/CLK_OUT3/EMAC_RXD2_35") (pintype "bidirectional"))
    )
    (net (code "81") (name "/Test_sig_n") (class "Default")
      (node (ref "R2") (pin "1") (pinfunction "1_1") (pintype "passive"))
      (node (ref "U4") (pin "114") (pinfunction "IO_L65N_SCP2_0_114") (pintype "bidirectional"))
    )
    (net (code "82") (name "/Test_sig_p") (class "Default")
      (node (ref "R5") (pin "1") (pinfunction "1_1") (pintype "passive"))
      (node (ref "U4") (pin "115") (pinfunction "IO_L65P_SCP3_0_115") (pintype "bidirectional"))
    )
    (net (code "83") (name "AD3V3A") (class "Default")
      (node (ref "C16") (pin "2") (pinfunction "2_2") (pintype "passive"))
      (node (ref "C36") (pin "2") (pinfunction "2_2") (pintype "passive"))
      (node (ref "C38") (pin "+") (pinfunction "+_+") (pintype "passive"))
      (node (ref "C57") (pin "1") (pinfunction "1_1") (pintype "passive"))
      (node (ref "U1") (pin "3") (pinfunction "Out_3") (pintype "passive"))
      (node (ref "U5") (pin "35") (pinfunction "AVDD_35") (pintype "power_in"))
      (node (ref "U5") (pin "40") (pinfunction "AVDD_40") (pintype "power_in"))
      (node (ref "U5") (pin "43") (pinfunction "AVDD_43") (pintype "power_in"))
      (node (ref "U5") (pin "58") (pinfunction "CLKVDD_58") (pintype "power_in"))
    )
    (net (code "84") (name "AD3V3D") (class "Default")
      (node (ref "C17") (pin "1") (pinfunction "1_1") (pintype "passive"))
      (node (ref "C35") (pin "1") (pinfunction "1_1") (pintype "passive"))
      (node (ref "C39") (pin "+") (pinfunction "+_+") (pintype "passive"))
      (node (ref "C45") (pin "1") (pinfunction "1_1") (pintype "passive"))
      (node (ref "R62") (pin "1") (pinfunction "1_1") (pintype "passive"))
      (node (ref "U2") (pin "3") (pinfunction "Out_3") (pintype "passive"))
      (node (ref "U5") (pin "17") (pinfunction "DRVDD_17") (pintype "power_in"))
      (node (ref "U5") (pin "60") (pinfunction "DVDD_60") (pintype "power_in"))
      (node (ref "U5") (pin "64") (pinfunction "DRVDD_64") (pintype "power_in"))
    )
    (net (code "85") (name "D1V2") (class "Default")
      (node (ref "C79") (pin "2") (pinfunction "2_2") (pintype "passive"))
      (node (ref "C86") (pin "+") (pinfunction "+_+") (pintype "passive"))
      (node (ref "C93") (pin "2") (pinfunction "2_2") (pintype "passive"))
      (node (ref "U13") (pin "3") (pinfunction "Out_3") (pintype "passive"))
      (node (ref "U4") (pin "128") (pinfunction "VCCINT_128") (pintype "power_in"))
      (node (ref "U4") (pin "19") (pinfunction "VCCINT_19") (pintype "power_in"))
      (node (ref "U4") (pin "28") (pinfunction "VCCINT_28") (pintype "power_in"))
      (node (ref "U4") (pin "52") (pinfunction "VCCINT_52") (pintype "power_in"))
      (node (ref "U4") (pin "89") (pinfunction "VCCINT_89") (pintype "power_in"))
    )
    (net (code "86") (name "D3V3") (class "Default")
      (node (ref "C21") (pin "1") (pinfunction "1_1") (pintype "passive"))
      (node (ref "C26") (pin "2") (pinfunction "2_2") (pintype "passive"))
      (node (ref "C46") (pin "2") (pinfunction "2_2") (pintype "passive"))
      (node (ref "C60") (pin "2") (pinfunction "2_2") (pintype "passive"))
      (node (ref "C74") (pin "2") (pinfunction "2_2") (pintype "passive"))
      (node (ref "C75") (pin "2") (pinfunction "2_2") (pintype "passive"))
      (node (ref "C85") (pin "+") (pinfunction "+_+") (pintype "passive"))
      (node (ref "C91") (pin "2") (pinfunction "2_2") (pintype "passive"))
      (node (ref "J3") (pin "1") (pinfunction "1_1") (pintype "passive"))
      (node (ref "Osc1") (pin "1") (pinfunction "Vcc_1") (pintype "passive"))
      (node (ref "R112") (pin "2") (pinfunction "2_2") (pintype "passive"))
      (node (ref "R113") (pin "2") (pinfunction "2_2") (pintype "passive"))
      (node (ref "R118") (pin "2") (pinfunction "2_2") (pintype "passive"))
      (node (ref "R121") (pin "1") (pinfunction "1_1") (pintype "passive"))
      (node (ref "R126") (pin "2") (pinfunction "2_2") (pintype "passive"))
      (node (ref "R128") (pin "2") (pinfunction "2_2") (pintype "passive"))
      (node (ref "R147") (pin "2") (pinfunction "2_2") (pintype "passive"))
      (node (ref "R151") (pin "2") (pinfunction "2_2") (pintype "passive"))
      (node (ref "R45") (pin "2") (pinfunction "2_2") (pintype "passive"))
      (node (ref "U10") (pin "8") (pinfunction "Vcc_8") (pintype "passive"))
      (node (ref "U12") (pin "3") (pinfunction "Out_3") (pintype "passive"))
      (node (ref "U13") (pin "1") (pinfunction "In_1") (pintype "passive"))
      (node (ref "U4") (pin "103") (pinfunction "VCCO_1_103") (pintype "power_in"))
      (node (ref "U4") (pin "122") (pinfunction "VCCO_0_122") (pintype "power_in"))
      (node (ref "U4") (pin "125") (pinfunction "VCCO_0_125") (pintype "power_in"))
      (node (ref "U4") (pin "129") (pinfunction "VCCAUX_129") (pintype "power_in"))
      (node (ref "U4") (pin "135") (pinfunction "VCCO_0_135") (pintype "power_in"))
      (node (ref "U4") (pin "18") (pinfunction "VCCO_3_18") (pintype "power_in"))
      (node (ref "U4") (pin "20") (pinfunction "VCCAUX_20") (pintype "power_in"))
      (node (ref "U4") (pin "31") (pinfunction "VCCO_3_31") (pintype "power_in"))
      (node (ref "U4") (pin "36") (pinfunction "VCCAUX_36") (pintype "power_in"))
      (node (ref "U4") (pin "4") (pinfunction "VCCO_3_4") (pintype "power_in"))
      (node (ref "U4") (pin "42") (pinfunction "VCCO_2_42") (pintype "power_in"))
      (node (ref "U4") (pin "53") (pinfunction "VCCAUX_53") (pintype "power_in"))
      (node (ref "U4") (pin "63") (pinfunction "VCCO_2_63") (pintype "power_in"))
      (node (ref "U4") (pin "69") (pinfunction "IO_L1N_M0_CMPMISO_2_69") (pintype "bidirectional"))
      (node (ref "U4") (pin "76") (pinfunction "VCCO_1_76") (pintype "power_in"))
      (node (ref "U4") (pin "86") (pinfunction "VCCO_1_86") (pintype "power_in"))
      (node (ref "U4") (pin "90") (pinfunction "VCCAUX_90") (pintype "power_in"))
    )
    (net (code "87") (name "ESP3V3") (class "Default")
      (node (ref "C2") (pin "+") (pinfunction "+_+") (pintype "passive"))
      (node (ref "C4") (pin "2") (pinfunction "2_2") (pintype "passive"))
      (node (ref "M1") (pin "2") (pinfunction "3V3_2") (pintype "power_in"))
      (node (ref "R6") (pin "2") (pinfunction "2_2") (pintype "passive"))
      (node (ref "R7") (pin "2") (pinfunction "2_2") (pintype "passive"))
      (node (ref "U3") (pin "3") (pinfunction "Out_3") (pintype "passive"))
    )
    (net (code "88") (name "GND") (class "Default")
      (node (ref "C16") (pin "1") (pinfunction "1_1") (pintype "passive"))
      (node (ref "C17") (pin "2") (pinfunction "2_2") (pintype "passive"))
      (node (ref "C2") (pin "-") (pinfunction "-_-") (pintype "passive"))
      (node (ref "C21") (pin "2") (pinfunction "2_2") (pintype "passive"))
      (node (ref "C26") (pin "1") (pinfunction "1_1") (pintype "passive"))
      (node (ref "C3") (pin "1") (pinfunction "1_1") (pintype "passive"))
      (node (ref "C35") (pin "2") (pinfunction "2_2") (pintype "passive"))
      (node (ref "C36") (pin "1") (pinfunction "1_1") (pintype "passive"))
      (node (ref "C38") (pin "-") (pinfunction "-_-") (pintype "passive"))
      (node (ref "C39") (pin "-") (pinfunction "-_-") (pintype "passive"))
      (node (ref "C4") (pin "1") (pinfunction "1_1") (pintype "passive"))
      (node (ref "C40") (pin "-") (pinfunction "-_-") (pintype "passive"))
      (node (ref "C45") (pin "2") (pinfunction "2_2") (pintype "passive"))
      (node (ref "C46") (pin "1") (pinfunction "1_1") (pintype "passive"))
      (node (ref "C5") (pin "1") (pinfunction "1_1") (pintype "passive"))
      (node (ref "C50") (pin "2") (pinfunction "2_2") (pintype "passive"))
      (node (ref "C57") (pin "2") (pinfunction "2_2") (pintype "passive"))
      (node (ref "C60") (pin "1") (pinfunction "1_1") (pintype "passive"))
      (node (ref "C67") (pin "2") (pinfunction "2_2") (pintype "passive"))
      (node (ref "C68") (pin "1") (pinfunction "1_1") (pintype "passive"))
      (node (ref "C74") (pin "1") (pinfunction "1_1") (pintype "passive"))
      (node (ref "C75") (pin "1") (pinfunction "1_1") (pintype "passive"))
      (node (ref "C79") (pin "1") (pinfunction "1_1") (pintype "passive"))
      (node (ref "C85") (pin "-") (pinfunction "-_-") (pintype "passive"))
      (node (ref "C86") (pin "-") (pinfunction "-_-") (pintype "passive"))
      (node (ref "C91") (pin "1") (pinfunction "1_1") (pintype "passive"))
      (node (ref "C93") (pin "1") (pinfunction "1_1") (pintype "passive"))
      (node (ref "D20") (pin "2") (pinfunction "2_2") (pintype "passive"))
      (node (ref "J1") (pin "3") (pinfunction "3_3") (pintype "passive"))
      (node (ref "J3") (pin "2") (pinfunction "2_2") (pintype "passive"))
      (node (ref "J7") (pin "1") (pinfunction "1_1") (pintype "passive"))
      (node (ref "M1") (pin "1") (pinfunction "GND_1") (pintype "power_in"))
      (node (ref "M1") (pin "15") (pinfunction "GND_15") (pintype "power_in"))
      (node (ref "M1") (pin "38") (pinfunction "GND_38") (pintype "power_in"))
      (node (ref "M1") (pin "39") (pinfunction "EP_39") (pintype "power_in"))
      (node (ref "Osc1") (pin "4") (pinfunction "Gnd_4") (pintype "passive"))
      (node (ref "R1") (pin "2") (pinfunction "2_2") (pintype "passive"))
      (node (ref "R127") (pin "1") (pinfunction "1_1") (pintype "passive"))
      (node (ref "R4") (pin "2") (pinfunction "2_2") (pintype "passive"))
      (node (ref "R73") (pin "2") (pinfunction "2_2") (pintype "passive"))
      (node (ref "SW1") (pin "2") (pinfunction "2_2") (pintype "passive"))
      (node (ref "SW2") (pin "1") (pinfunction "1_1") (pintype "passive"))
      (node (ref "U1") (pin "2") (pinfunction "Gnd_2") (pintype "passive"))
      (node (ref "U10") (pin "4") (pinfunction "Gnd_4") (pintype "passive"))
      (node (ref "U12") (pin "2") (pinfunction "Gnd_2") (pintype "passive"))
      (node (ref "U13") (pin "2") (pinfunction "Gnd_2") (pintype "passive"))
      (node (ref "U2") (pin "2") (pinfunction "Gnd_2") (pintype "passive"))
      (node (ref "U3") (pin "2") (pinfunction "Gnd_2") (pintype "passive"))
      (node (ref "U4") (pin "108") (pinfunction "GND_108") (pintype "power_in"))
      (node (ref "U4") (pin "113") (pinfunction "GND_113") (pintype "power_in"))
      (node (ref "U4") (pin "126") (pinfunction "IO_L36N_GCLK14_0_126") (pintype "bidirectional"))
      (node (ref "U4") (pin "13") (pinfunction "GND_13") (pintype "power_in"))
      (node (ref "U4") (pin "130") (pinfunction "GND_130") (pintype "power_in"))
      (node (ref "U4") (pin "136") (pinfunction "GND_136") (pintype "power_in"))
      (node (ref "U4") (pin "144") (pinfunction "IO_L1P_HSWAPEN_0_144") (pintype "bidirectional"))
      (node (ref "U4") (pin "25") (pinfunction "GND_25") (pintype "power_in"))
      (node (ref "U4") (pin "3") (pinfunction "GND_3") (pintype "power_in"))
      (node (ref "U4") (pin "49") (pinfunction "GND_49") (pintype "power_in"))
      (node (ref "U4") (pin "54") (pinfunction "GND_54") (pintype "power_in"))
      (node (ref "U4") (pin "60") (pinfunction "IO_L13P_M1_2_60") (pintype "bidirectional"))
      (node (ref "U4") (pin "68") (pinfunction "GND_68") (pintype "power_in"))
      (node (ref "U4") (pin "73") (pinfunction "SUSPEND_73") (pintype "input"))
      (node (ref "U4") (pin "77") (pinfunction "GND_77") (pintype "power_in"))
      (node (ref "U4") (pin "91") (pinfunction "GND_91") (pintype "power_in"))
      (node (ref "U4") (pin "96") (pinfunction "GND_96") (pintype "power_in"))
      (node (ref "U5") (pin "18") (pinfunction "DRVSS_18") (pintype "power_in"))
      (node (ref "U5") (pin "31") (pinfunction "AVSS_31") (pintype "power_in"))
      (node (ref "U5") (pin "34") (pinfunction "AVSS_34") (pintype "power_in"))
      (node (ref "U5") (pin "36") (pinfunction "AVSS_36") (pintype "power_in"))
      (node (ref "U5") (pin "39") (pinfunction "AVSS_39") (pintype "power_in"))
      (node (ref "U5") (pin "44") (pinfunction "AVSS_44") (pintype "power_in"))
      (node (ref "U5") (pin "47") (pinfunction "AVSS_47") (pintype "power_in"))
      (node (ref "U5") (pin "48") (pinfunction "AVSS_48") (pintype "power_in"))
      (node (ref "U5") (pin "55") (pinfunction "CLKVSS_55") (pintype "power_in"))
      (node (ref "U5") (pin "59") (pinfunction "DVSS_59") (pintype "power_in"))
      (node (ref "U5") (pin "63") (pinfunction "DRVSS_63") (pintype "power_in"))
      (node (ref "U5") (pin "65") (pinfunction "EP_65") (pintype "passive"))
    )
    (net (code "89") (name "Net-(D20-Pad1)") (class "Default")
      (node (ref "D20") (pin "1") (pinfunction "1_1") (pintype "passive"))
      (node (ref "R123") (pin "2") (pinfunction "2_2") (pintype "passive"))
    )
    (net (code "90") (name "Net-(M1-EN)") (class "Default")
      (node (ref "C5") (pin "2") (pinfunction "2_2") (pintype "passive"))
      (node (ref "M1") (pin "3") (pinfunction "EN_3") (pintype "bidirectional"))
      (node (ref "R6") (pin "1") (pinfunction "1_1") (pintype "passive"))
      (node (ref "SW1") (pin "1") (pinfunction "1_1") (pintype "passive"))
    )
    (net (code "91") (name "Net-(M1-IO0{slash}GPIO0{slash}ADC2_CH1{slash}TOUCH1{slash}RTC_GPIO11{slash}CLK_OUT1{slash}EMAC_TX_CLK)") (class "Default")
      (node (ref "M1") (pin "25") (pinfunction "IO0/GPIO0/ADC2_CH1/TOUCH1/RTC_GPIO11/CLK_OUT1/EMAC_TX_CLK_25") (pintype "bidirectional"))
      (node (ref "R7") (pin "1") (pinfunction "1_1") (pintype "passive"))
      (node (ref "SW2") (pin "2") (pinfunction "2_2") (pintype "passive"))
    )
    (net (code "92") (name "Net-(Osc1-En)") (class "Default")
      (node (ref "Osc1") (pin "2") (pinfunction "En_2") (pintype "passive"))
      (node (ref "R45") (pin "1") (pinfunction "1_1") (pintype "passive"))
    )
    (net (code "93") (name "Net-(Osc1-Out)") (class "Default")
      (node (ref "Osc1") (pin "3") (pinfunction "Out_3") (pintype "passive"))
      (node (ref "R44") (pin "2") (pinfunction "2_2") (pintype "passive"))
    )
    (net (code "94") (name "Net-(U4E-CMPCS_B_2)") (class "Default")
      (node (ref "R118") (pin "1") (pinfunction "1_1") (pintype "passive"))
      (node (ref "U4") (pin "72") (pinfunction "CMPCS_B_2_72") (pintype "input"))
    )
    (net (code "95") (name "Net-(U5A-REFADJ)") (class "Default")
      (node (ref "R73") (pin "1") (pinfunction "1_1") (pintype "passive"))
      (node (ref "U5") (pin "41") (pinfunction "REFADJ_41") (pintype "input"))
    )
    (net (code "96") (name "Net-(U5A-REFB)") (class "Default")
      (node (ref "C61") (pin "1") (pinfunction "1_1") (pintype "passive"))
      (node (ref "C62") (pin "1") (pinfunction "1_1") (pintype "passive"))
      (node (ref "C67") (pin "1") (pinfunction "1_1") (pintype "passive"))
      (node (ref "U5") (pin "32") (pinfunction "REFB_32") (pintype "passive"))
    )
    (net (code "97") (name "Net-(U5A-REFIO)") (class "Default")
      (node (ref "C50") (pin "1") (pinfunction "1_1") (pintype "passive"))
      (node (ref "U5") (pin "42") (pinfunction "REFIO_42") (pintype "bidirectional"))
    )
    (net (code "98") (name "Net-(U5A-REFT)") (class "Default")
      (node (ref "C61") (pin "2") (pinfunction "2_2") (pintype "passive"))
      (node (ref "C62") (pin "2") (pinfunction "2_2") (pintype "passive"))
      (node (ref "C68") (pin "2") (pinfunction "2_2") (pintype "passive"))
      (node (ref "U5") (pin "33") (pinfunction "REFT_33") (pintype "passive"))
    )
    (net (code "99") (name "unconnected-(M1-SCK{slash}CLK*{slash}GPIO6{slash}SD_CLK{slash}SPICLK{slash}HS1_CLK{slash}U1CTS-Pad20)") (class "Default")
      (node (ref "M1") (pin "20") (pinfunction "SCK/CLK*/GPIO6/SD_CLK/SPICLK/HS1_CLK/U1CTS_20") (pintype "bidirectional"))
    )
    (net (code "100") (name "unconnected-(M1-SCS{slash}CMD*{slash}GPIO11{slash}SD_CMD{slash}SPICS0{slash}HS1_CMD{slash}U1RTS-Pad19)") (class "Default")
      (node (ref "M1") (pin "19") (pinfunction "SCS/CMD*/GPIO11/SD_CMD/SPICS0/HS1_CMD/U1RTS_19") (pintype "bidirectional"))
    )
    (net (code "101") (name "unconnected-(M1-SDI{slash}SD1*{slash}GPIO8{slash}SD_DATA1{slash}SPID{slash}HS1_DATA1{slash}U2CTS-Pad22)") (class "Default")
      (node (ref "M1") (pin "22") (pinfunction "SDI/SD1*/GPIO8/SD_DATA1/SPID/HS1_DATA1/U2CTS_22") (pintype "bidirectional"))
    )
    (net (code "102") (name "unconnected-(M1-SDO{slash}SD0*{slash}GPIO7{slash}SD_DATA0{slash}SPIQ{slash}HS1_DATA0{slash}U2RTS-Pad21)") (class "Default")
      (node (ref "M1") (pin "21") (pinfunction "SDO/SD0*/GPIO7/SD_DATA0/SPIQ/HS1_DATA0/U2RTS_21") (pintype "bidirectional"))
    )
    (net (code "103") (name "unconnected-(M1-SHD{slash}SD2*{slash}GPIO9{slash}SD_DATA2{slash}SPIHD{slash}HS1_DATA2{slash}U1RXD-Pad17)") (class "Default")
      (node (ref "M1") (pin "17") (pinfunction "SHD/SD2*/GPIO9/SD_DATA2/SPIHD/HS1_DATA2/U1RXD_17") (pintype "bidirectional"))
    )
    (net (code "104") (name "unconnected-(M1-SWP{slash}SD3*{slash}GPIO10{slash}SD_DATA3{slash}SPIWP{slash}HS1_DATA3{slash}U1TXD-Pad18)") (class "Default")
      (node (ref "M1") (pin "18") (pinfunction "SWP/SD3*/GPIO10/SD_DATA3/SPIWP/HS1_DATA3/U1TXD_18") (pintype "bidirectional"))
    )
    (net (code "105") (name "unconnected-(U4A-IO_L1N_VREF_0-Pad143)") (class "Default")
      (node (ref "U4") (pin "143") (pinfunction "IO_L1N_VREF_0_143") (pintype "bidirectional"))
    )
    (net (code "106") (name "unconnected-(U4A-IO_L2N_0-Pad141)") (class "Default")
      (node (ref "U4") (pin "141") (pinfunction "IO_L2N_0_141") (pintype "bidirectional"))
    )
    (net (code "107") (name "unconnected-(U4A-IO_L2P_0-Pad142)") (class "Default")
      (node (ref "U4") (pin "142") (pinfunction "IO_L2P_0_142") (pintype "bidirectional"))
    )
    (net (code "108") (name "unconnected-(U4A-IO_L3N_0-Pad139)") (class "Default")
      (node (ref "U4") (pin "139") (pinfunction "IO_L3N_0_139") (pintype "bidirectional"))
    )
    (net (code "109") (name "unconnected-(U4A-IO_L3P_0-Pad140)") (class "Default")
      (node (ref "U4") (pin "140") (pinfunction "IO_L3P_0_140") (pintype "bidirectional"))
    )
    (net (code "110") (name "unconnected-(U4A-IO_L4N_0-Pad137)") (class "Default")
      (node (ref "U4") (pin "137") (pinfunction "IO_L4N_0_137") (pintype "bidirectional"))
    )
    (net (code "111") (name "unconnected-(U4A-IO_L4P_0-Pad138)") (class "Default")
      (node (ref "U4") (pin "138") (pinfunction "IO_L4P_0_138") (pintype "bidirectional"))
    )
    (net (code "112") (name "unconnected-(U4A-IO_L34N_GCLK18_0-Pad133)") (class "Default")
      (node (ref "U4") (pin "133") (pinfunction "IO_L34N_GCLK18_0_133") (pintype "bidirectional"))
    )
    (net (code "113") (name "unconnected-(U4A-IO_L37N_GCLK12_0-Pad123)") (class "Default")
      (node (ref "U4") (pin "123") (pinfunction "IO_L37N_GCLK12_0_123") (pintype "bidirectional"))
    )
    (net (code "114") (name "unconnected-(U4A-IO_L62N_VREF_0-Pad120)") (class "Default")
      (node (ref "U4") (pin "120") (pinfunction "IO_L62N_VREF_0_120") (pintype "bidirectional"))
    )
    (net (code "115") (name "unconnected-(U4A-IO_L62P_0-Pad121)") (class "Default")
      (node (ref "U4") (pin "121") (pinfunction "IO_L62P_0_121") (pintype "bidirectional"))
    )
    (net (code "116") (name "unconnected-(U4A-IO_L63N_SCP6_0-Pad118)") (class "Default")
      (node (ref "U4") (pin "118") (pinfunction "IO_L63N_SCP6_0_118") (pintype "bidirectional"))
    )
    (net (code "117") (name "unconnected-(U4A-IO_L63P_SCP7_0-Pad119)") (class "Default")
      (node (ref "U4") (pin "119") (pinfunction "IO_L63P_SCP7_0_119") (pintype "bidirectional"))
    )
    (net (code "118") (name "unconnected-(U4A-IO_L64N_SCP4_0-Pad116)") (class "Default")
      (node (ref "U4") (pin "116") (pinfunction "IO_L64N_SCP4_0_116") (pintype "bidirectional"))
    )
    (net (code "119") (name "unconnected-(U4A-IO_L64P_SCP5_0-Pad117)") (class "Default")
      (node (ref "U4") (pin "117") (pinfunction "IO_L64P_SCP5_0_117") (pintype "bidirectional"))
    )
    (net (code "120") (name "unconnected-(U4A-IO_L66P_SCP1_0-Pad112)") (class "Default")
      (node (ref "U4") (pin "112") (pinfunction "IO_L66P_SCP1_0_112") (pintype "bidirectional"))
    )
    (net (code "121") (name "unconnected-(U4C-IO_L2N_CMPMOSI_2-Pad66)") (class "Default")
      (node (ref "U4") (pin "66") (pinfunction "IO_L2N_CMPMOSI_2_66") (pintype "bidirectional+no_connect"))
    )
    (net (code "122") (name "unconnected-(U4C-IO_L2P_CMPCLK_2-Pad67)") (class "Default")
      (node (ref "U4") (pin "67") (pinfunction "IO_L2P_CMPCLK_2_67") (pintype "bidirectional+no_connect"))
    )
    (net (code "123") (name "unconnected-(U4C-IO_L13N_D10_2-Pad59)") (class "Default")
      (node (ref "U4") (pin "59") (pinfunction "IO_L13N_D10_2_59") (pintype "bidirectional"))
    )
    (net (code "124") (name "unconnected-(U4C-IO_L14N_D12_2-Pad57)") (class "Default")
      (node (ref "U4") (pin "57") (pinfunction "IO_L14N_D12_2_57") (pintype "bidirectional"))
    )
    (net (code "125") (name "unconnected-(U4C-IO_L14P_D11_2-Pad58)") (class "Default")
      (node (ref "U4") (pin "58") (pinfunction "IO_L14P_D11_2_58") (pintype "bidirectional"))
    )
    (net (code "126") (name "unconnected-(U4C-IO_L30N_GCLK0_USERCCLK_2-Pad55)") (class "Default")
      (node (ref "U4") (pin "55") (pinfunction "IO_L30N_GCLK0_USERCCLK_2_55") (pintype "bidirectional"))
    )
    (net (code "127") (name "unconnected-(U4C-IO_L30P_GCLK1_D13_2-Pad56)") (class "Default")
      (node (ref "U4") (pin "56") (pinfunction "IO_L30P_GCLK1_D13_2_56") (pintype "bidirectional"))
    )
    (net (code "128") (name "unconnected-(U4C-IO_L31N_GCLK30_D15_2-Pad50)") (class "Default")
      (node (ref "U4") (pin "50") (pinfunction "IO_L31N_GCLK30_D15_2_50") (pintype "bidirectional"))
    )
    (net (code "129") (name "unconnected-(U4C-IO_L31P_GCLK31_D14_2-Pad51)") (class "Default")
      (node (ref "U4") (pin "51") (pinfunction "IO_L31P_GCLK31_D14_2_51") (pintype "bidirectional"))
    )
    (net (code "130") (name "unconnected-(U4C-IO_L48N_RDWR_B_VREF_2-Pad47)") (class "Default")
      (node (ref "U4") (pin "47") (pinfunction "IO_L48N_RDWR_B_VREF_2_47") (pintype "bidirectional"))
    )
    (net (code "131") (name "unconnected-(U4C-IO_L48P_D7_2-Pad48)") (class "Default")
      (node (ref "U4") (pin "48") (pinfunction "IO_L48P_D7_2_48") (pintype "bidirectional"))
    )
    (net (code "132") (name "unconnected-(U4C-IO_L49N_D4_2-Pad45)") (class "Default")
      (node (ref "U4") (pin "45") (pinfunction "IO_L49N_D4_2_45") (pintype "bidirectional"))
    )
    (net (code "133") (name "unconnected-(U4C-IO_L49P_D3_2-Pad46)") (class "Default")
      (node (ref "U4") (pin "46") (pinfunction "IO_L49P_D3_2_46") (pintype "bidirectional"))
    )
    (net (code "134") (name "unconnected-(U4C-IO_L62N_D6_2-Pad43)") (class "Default")
      (node (ref "U4") (pin "43") (pinfunction "IO_L62N_D6_2_43") (pintype "bidirectional"))
    )
    (net (code "135") (name "unconnected-(U4C-IO_L62P_D5_2-Pad44)") (class "Default")
      (node (ref "U4") (pin "44") (pinfunction "IO_L62P_D5_2_44") (pintype "bidirectional"))
    )
    (net (code "136") (name "unconnected-(U4C-IO_L64N_D9_2-Pad40)") (class "Default")
      (node (ref "U4") (pin "40") (pinfunction "IO_L64N_D9_2_40") (pintype "bidirectional"))
    )
    (net (code "137") (name "unconnected-(U4C-IO_L64P_D8_2-Pad41)") (class "Default")
      (node (ref "U4") (pin "41") (pinfunction "IO_L64P_D8_2_41") (pintype "bidirectional"))
    )
    (net (code "138") (name "unconnected-(U4D-IO_L43N_GCLK22_IRDY2_3-Pad16)") (class "Default")
      (node (ref "U4") (pin "16") (pinfunction "IO_L43N_GCLK22_IRDY2_3_16") (pintype "bidirectional"))
    )
    (net (code "139") (name "unconnected-(U4D-IO_L43P_GCLK23_3-Pad17)") (class "Default")
      (node (ref "U4") (pin "17") (pinfunction "IO_L43P_GCLK23_3_17") (pintype "bidirectional"))
    )
    (net (code "140") (name "unconnected-(U4D-IO_L44N_GCLK20_3-Pad14)") (class "Default")
      (node (ref "U4") (pin "14") (pinfunction "IO_L44N_GCLK20_3_14") (pintype "bidirectional"))
    )
    (net (code "141") (name "unconnected-(U4D-IO_L44P_GCLK21_3-Pad15)") (class "Default")
      (node (ref "U4") (pin "15") (pinfunction "IO_L44P_GCLK21_3_15") (pintype "bidirectional"))
    )
    (net (code "142") (name "unconnected-(U4D-IO_L49N_3-Pad11)") (class "Default")
      (node (ref "U4") (pin "11") (pinfunction "IO_L49N_3_11") (pintype "bidirectional"))
    )
    (net (code "143") (name "unconnected-(U4D-IO_L49P_3-Pad12)") (class "Default")
      (node (ref "U4") (pin "12") (pinfunction "IO_L49P_3_12") (pintype "bidirectional"))
    )
    (net (code "144") (name "unconnected-(U4D-IO_L50N_3-Pad9)") (class "Default")
      (node (ref "U4") (pin "9") (pinfunction "IO_L50N_3_9") (pintype "bidirectional"))
    )
    (net (code "145") (name "unconnected-(U4D-IO_L50P_3-Pad10)") (class "Default")
      (node (ref "U4") (pin "10") (pinfunction "IO_L50P_3_10") (pintype "bidirectional"))
    )
    (net (code "146") (name "unconnected-(U4D-IO_L51N_3-Pad7)") (class "Default")
      (node (ref "U4") (pin "7") (pinfunction "IO_L51N_3_7") (pintype "bidirectional"))
    )
    (net (code "147") (name "unconnected-(U4D-IO_L51P_3-Pad8)") (class "Default")
      (node (ref "U4") (pin "8") (pinfunction "IO_L51P_3_8") (pintype "bidirectional"))
    )
    (net (code "148") (name "unconnected-(U4D-IO_L52N_3-Pad5)") (class "Default")
      (node (ref "U4") (pin "5") (pinfunction "IO_L52N_3_5") (pintype "bidirectional"))
    )
    (net (code "149") (name "unconnected-(U4D-IO_L52P_3-Pad6)") (class "Default")
      (node (ref "U4") (pin "6") (pinfunction "IO_L52P_3_6") (pintype "bidirectional"))
    )
    (net (code "150") (name "unconnected-(U4D-IO_L83N_VREF_3-Pad1)") (class "Default")
      (node (ref "U4") (pin "1") (pinfunction "IO_L83N_VREF_3_1") (pintype "bidirectional"))
    )
    (net (code "151") (name "unconnected-(U4D-IO_L83P_3-Pad2)") (class "Default")
      (node (ref "U4") (pin "2") (pinfunction "IO_L83P_3_2") (pintype "bidirectional"))
    )
    (net (code "152") (name "unconnected-(U5A-NC{slash}Rx[0]-Pad12)") (class "Default")
      (node (ref "U5") (pin "12") (pinfunction "NC/Rx[0]_12") (pintype "tri_state"))
    )
    (net (code "153") (name "unconnected-(U5A-NC{slash}Rx[1]-Pad11)") (class "Default")
      (node (ref "U5") (pin "11") (pinfunction "NC/Rx[1]_11") (pintype "tri_state"))
    )
    (net (code "154") (name "unconnected-(U5A-XTAL-Pad56)") (class "Default")
      (node (ref "U5") (pin "56") (pinfunction "XTAL_56") (pintype "output"))
    )
  )
)
